# SCE.net
KiCad netlist of a schematic drawn in Altium Designer
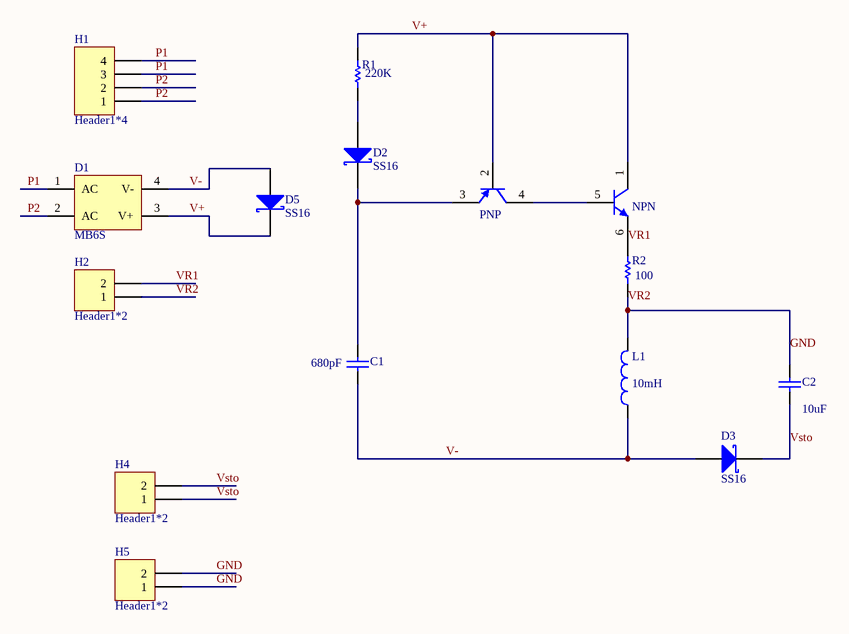
[diagram p0: SCE.SchDoc]

(export (version "E")
  (design (tool "Eeschema 10.0.6"))
  (components
    (comp (ref "C1")
      (value "680pF")
      (footprint "RAD-0.1")
      (description "Capacitor")
      (fields (field (name "Comment") "Cap") (field (name "PUBLISHER") "Altium Limited"))
      (libsource (lib "Miscellaneous Devices") (part "Cap"))
    )
    (comp (ref "C2")
      (value "10uF")
      (footprint "RB")
      (description "Capacitor")
      (fields (field (name "Comment") "Cap") (field (name "PUBLISHER") "Altium Limited"))
      (libsource (lib "Miscellaneous Devices") (part "Cap"))
    )
    (comp (ref "D1")
      (value "MB6S")
      (footprint "MB6S")
      (description "Diode Bridge")
      (fields (field (name "PUBLISHER") "Altium Limited"))
      (libsource (lib "Schlib1") (part "MB6S"))
    )
    (comp (ref "D2")
      (value "SS16")
      (footprint "SS16")
      (description "Schottky Diode")
      (fields (field (name "PUBLISHER") "Altium Limited"))
      (libsource (lib "Schlib1") (part "SS16"))
    )
    (comp (ref "D3")
      (value "SS16")
      (footprint "SS16")
      (description "Schottky Diode")
      (fields (field (name "PUBLISHER") "Altium Limited"))
      (libsource (lib "Schlib1") (part "SS16"))
    )
    (comp (ref "D4")
      (value "NPN")
      (footprint "xn4601")
      (description "Composite Transistors")
      (libsource (lib "Schlib1") (part "XN4601"))
    )
    (comp (ref "D5")
      (value "SS16")
      (footprint "SS16")
      (description "Schottky Diode")
      (fields (field (name "PUBLISHER") "Altium Limited"))
      (libsource (lib "Schlib1") (part "SS16"))
    )
    (comp (ref "H1")
      (value "Header1*4")
      (footprint "Header1*4")
      (libsource (lib "Schlib1") (part "Header1*4"))
    )
    (comp (ref "H2")
      (value "Header1*2")
      (footprint "Header1*2")
      (libsource (lib "Schlib1") (part "Header1*2"))
    )
    (comp (ref "H4")
      (value "Header1*2")
      (footprint "Header1*2")
      (libsource (lib "Schlib1") (part "Header1*2"))
    )
    (comp (ref "H5")
      (value "Header1*2")
      (footprint "Header1*2")
      (libsource (lib "Schlib1") (part "Header1*2"))
    )
    (comp (ref "L1")
      (value "10mH")
      (footprint "Inductance")
      (description "Inductor")
      (fields (field (name "PUBLISHER") "Altium Limited"))
      (libsource (lib "Miscellaneous Devices") (part "Inductor"))
    )
    (comp (ref "R1")
      (value "220K")
      (footprint "RES")
      (description "Resistor")
      (fields (field (name "Comment") "Res1") (field (name "PUBLISHER") "Altium Limited"))
      (libsource (lib "Schlib1") (part "Res1"))
    )
    (comp (ref "R2")
      (value "100")
      (footprint "PcbLib1:res")
      (description "Resistor")
      (fields (field (name "Comment") "Res1") (field (name "PUBLISHER") "Altium Limited"))
      (libsource (lib "Schlib1") (part "Res1"))
    )
  )
  (nets
    (net (code "1") (name "/GND") (class "Default")
      (node (ref "C2") (pin "2") (pinfunction "2_2") (pintype "passive"))
      (node (ref "H2") (pin "1") (pinfunction "1_1") (pintype "passive"))
      (node (ref "H5") (pin "1") (pinfunction "1_1") (pintype "passive"))
      (node (ref "H5") (pin "2") (pinfunction "2_2") (pintype "passive"))
      (node (ref "L1") (pin "2") (pinfunction "2_2") (pintype "passive"))
      (node (ref "R2") (pin "1") (pinfunction "1_1") (pintype "passive"))
    )
    (net (code "2") (name "/P1") (class "Default")
      (node (ref "D1") (pin "1") (pinfunction "AC_1") (pintype "passive"))
      (node (ref "H1") (pin "3") (pinfunction "3_3") (pintype "passive"))
      (node (ref "H1") (pin "4") (pinfunction "4_4") (pintype "passive"))
    )
    (net (code "3") (name "/P2") (class "Default")
      (node (ref "D1") (pin "2") (pinfunction "AC_2") (pintype "passive"))
      (node (ref "H1") (pin "1") (pinfunction "1_1") (pintype "passive"))
      (node (ref "H1") (pin "2") (pinfunction "2_2") (pintype "passive"))
    )
    (net (code "4") (name "/V+") (class "Default")
      (node (ref "D1") (pin "3") (pinfunction "V+_3") (pintype "passive"))
      (node (ref "D4") (pin "1") (pinfunction "C_1") (pintype "passive"))
      (node (ref "D4") (pin "2") (pinfunction "B_2") (pintype "passive"))
      (node (ref "D5") (pin "2") (pinfunction "K_2") (pintype "passive"))
      (node (ref "R1") (pin "2") (pinfunction "2_2") (pintype "passive"))
    )
    (net (code "5") (name "/V-") (class "Default")
      (node (ref "C1") (pin "1") (pinfunction "1_1") (pintype "passive"))
      (node (ref "D1") (pin "4") (pinfunction "V-_4") (pintype "passive"))
      (node (ref "D3") (pin "1") (pinfunction "A_1") (pintype "passive"))
      (node (ref "D5") (pin "1") (pinfunction "A_1") (pintype "passive"))
      (node (ref "L1") (pin "1") (pinfunction "1_1") (pintype "passive"))
    )
    (net (code "6") (name "/VR1") (class "Default")
      (node (ref "D4") (pin "6") (pinfunction "E_6") (pintype "passive"))
      (node (ref "H2") (pin "2") (pinfunction "2_2") (pintype "passive"))
      (node (ref "R2") (pin "2") (pinfunction "2_2") (pintype "passive"))
    )
    (net (code "7") (name "/Vsto") (class "Default")
      (node (ref "C2") (pin "1") (pinfunction "1_1") (pintype "passive"))
      (node (ref "D3") (pin "2") (pinfunction "K_2") (pintype "passive"))
      (node (ref "H4") (pin "1") (pinfunction "1_1") (pintype "passive"))
      (node (ref "H4") (pin "2") (pinfunction "2_2") (pintype "passive"))
    )
    (net (code "8") (name "Net-(D2-A)") (class "Default")
      (node (ref "D2") (pin "1") (pinfunction "A_1") (pintype "passive"))
      (node (ref "R1") (pin "1") (pinfunction "1_1") (pintype "passive"))
    )
    (net (code "9") (name "Net-(D2-K)") (class "Default")
      (node (ref "C1") (pin "2") (pinfunction "2_2") (pintype "passive"))
      (node (ref "D2") (pin "2") (pinfunction "K_2") (pintype "passive"))
      (node (ref "D4") (pin "3") (pinfunction "E_3") (pintype "passive"))
    )
    (net (code "10") (name "Net-(D4A-B)") (class "Default")
      (node (ref "D4") (pin "4") (pinfunction "C_4") (pintype "passive"))
      (node (ref "D4") (pin "5") (pinfunction "B_5") (pintype "passive"))
    )
  )
)
